# Schematic.net
KiCad netlist of a schematic drawn in Altium Designer
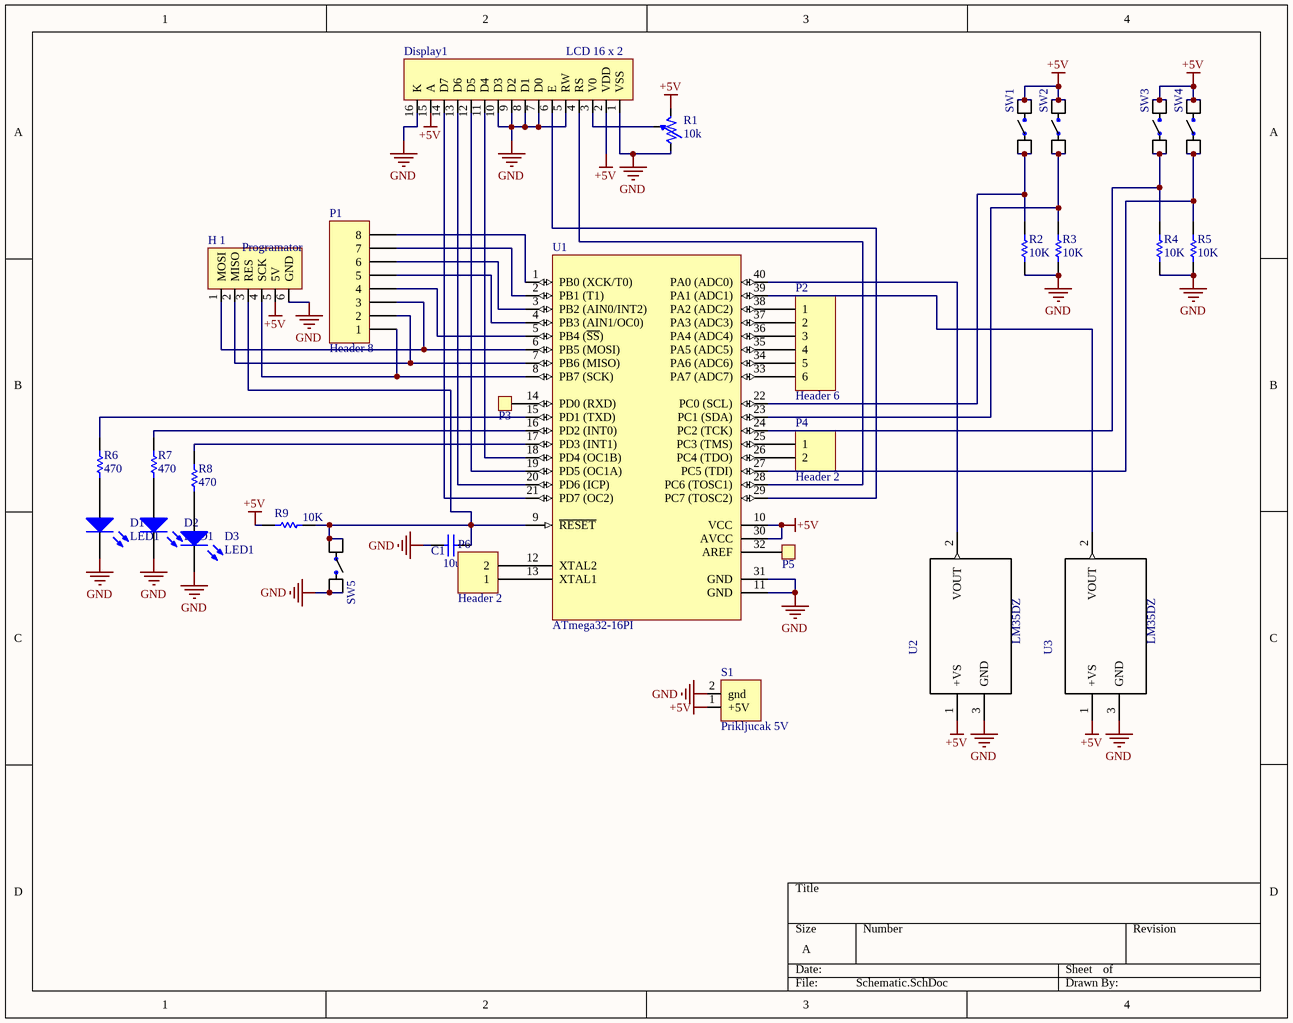
[diagram p0: Schematic.SchDoc]

(export (version "E")
  (design (tool "Eeschema 10.0.6"))
  (components
    (comp (ref "C1")
      (value "10uF")
      (footprint "RAD-0.3")
      (description "Capacitor")
      (fields (field (name "Comment") "Cap") (field (name "PUBLISHER") "Altium Limited"))
      (libsource (lib "Miscellaneous Devices") (part "Cap"))
    )
    (comp (ref "D1")
      (value "LED1")
      (footprint "LED-1")
      (description "Typical RED GaAs LED")
      (fields (field (name "PUBLISHER") "Altium Limited"))
      (libsource (lib "Miscellaneous Devices") (part "LED1"))
    )
    (comp (ref "D2")
      (value "LED1")
      (footprint "LED-1")
      (description "Typical RED GaAs LED")
      (fields (field (name "PUBLISHER") "Altium Limited"))
      (libsource (lib "Miscellaneous Devices") (part "LED1"))
    )
    (comp (ref "D3")
      (value "LED1")
      (footprint "LED-1")
      (description "Typical RED GaAs LED")
      (fields (field (name "PUBLISHER") "Altium Limited"))
      (libsource (lib "Miscellaneous Devices") (part "LED1"))
    )
    (comp (ref "Display1")
      (value "LCD 16 x 2")
      (footprint "LCD16x2")
      (libsource (lib "LIB-shematic") (part "LCD 16 X 2"))
    )
    (comp (ref "H 1")
      (value "Programator")
      (footprint "USBASP")
      (libsource (lib "LIB-shematic") (part "USBASP"))
    )
    (comp (ref "P1")
      (value "Header 8")
      (footprint "HDR1X8")
      (description "Header, 8-Pin")
      (fields (field (name "PUBLISHER") "Altium Limited"))
      (libsource (lib "Miscellaneous Connectors") (part "Header 8"))
    )
    (comp (ref "P2")
      (value "Header 6")
      (footprint "HDR1X6")
      (description "Header, 6-Pin")
      (fields (field (name "PUBLISHER") "Altium Limited"))
      (libsource (lib "Miscellaneous Connectors") (part "Header 6"))
    )
    (comp (ref "P3")
      (value "Header 1")
      (footprint "Header 1")
      (libsource (lib "LIB-schematic") (part "Header 1"))
    )
    (comp (ref "P4")
      (value "Header 2")
      (footprint "HDR1X2")
      (description "Header, 2-Pin")
      (fields (field (name "PUBLISHER") "Altium Limited"))
      (libsource (lib "") (part "Header 2_1"))
    )
    (comp (ref "P5")
      (value "Header 1")
      (footprint "Header 1")
      (libsource (lib "LIB-shematic") (part "Header 1"))
    )
    (comp (ref "P6")
      (value "Header 2")
      (footprint "HDR1X2")
      (description "Header, 2-Pin")
      (fields (field (name "PUBLISHER") "Altium Limited"))
      (libsource (lib "Miscellaneous Connectors") (part "Header 2"))
    )
    (comp (ref "R1") (value "10k") (footprint "ADJ_RES") (libsource (lib "LIB-shematic") (part "ADJ_RES")))
    (comp (ref "R2")
      (value "10K")
      (footprint "AXIAL-0.3")
      (description "Resistor")
      (fields (field (name "Comment") "Res1") (field (name "PUBLISHER") "Altium Limited"))
      (libsource (lib "Miscellaneous Devices") (part "Res1"))
    )
    (comp (ref "R3")
      (value "10K")
      (footprint "AXIAL-0.3")
      (description "Resistor")
      (fields (field (name "Comment") "Res1") (field (name "PUBLISHER") "Altium Limited"))
      (libsource (lib "Miscellaneous Devices") (part "Res1"))
    )
    (comp (ref "R4")
      (value "10K")
      (footprint "AXIAL-0.3")
      (description "Resistor")
      (fields (field (name "Comment") "Res1") (field (name "PUBLISHER") "Altium Limited"))
      (libsource (lib "Miscellaneous Devices") (part "Res1"))
    )
    (comp (ref "R5")
      (value "10K")
      (footprint "AXIAL-0.3")
      (description "Resistor")
      (fields (field (name "Comment") "Res1") (field (name "PUBLISHER") "Altium Limited"))
      (libsource (lib "Miscellaneous Devices") (part "Res1"))
    )
    (comp (ref "R6")
      (value "470")
      (footprint "AXIAL-0.3")
      (description "Resistor")
      (fields (field (name "Comment") "Res1") (field (name "PUBLISHER") "Altium Limited"))
      (libsource (lib "Miscellaneous Devices") (part "Res1"))
    )
    (comp (ref "R7")
      (value "470")
      (footprint "AXIAL-0.3")
      (description "Resistor")
      (fields (field (name "Comment") "Res1") (field (name "PUBLISHER") "Altium Limited"))
      (libsource (lib "Miscellaneous Devices") (part "Res1"))
    )
    (comp (ref "R8")
      (value "470")
      (footprint "AXIAL-0.3")
      (description "Resistor")
      (fields (field (name "Comment") "Res1") (field (name "PUBLISHER") "Altium Limited"))
      (libsource (lib "Miscellaneous Devices") (part "Res1"))
    )
    (comp (ref "R9")
      (value "10K")
      (footprint "AXIAL-0.3")
      (description "Resistor")
      (fields (field (name "Comment") "Res1") (field (name "PUBLISHER") "Altium Limited"))
      (libsource (lib "Miscellaneous Devices") (part "Res1"))
    )
    (comp (ref "S1")
      (value "Prikljucak 5V")
      (footprint "H 5V")
      (libsource (lib "LIB-schematic") (part "Header 5V"))
    )
    (comp (ref "SW1")
      (value "2-1437565-8")
      (footprint "*SW_SMD_2-1437565-8_4_4.50_6.00_6.00_5.00")
      (description "Tactile Switch SPST-NO Top Actuated Surface Mount")
      (fields (field (name "MF") "TE Connectivity"))
      (libsource (lib "LIB-shematic") (part "2-1437565-8"))
    )
    (comp (ref "SW2")
      (value "2-1437565-8")
      (footprint "*SW_SMD_2-1437565-8_4_4.50_6.00_6.00_5.00")
      (description "Tactile Switch SPST-NO Top Actuated Surface Mount")
      (fields (field (name "MF") "TE Connectivity"))
      (libsource (lib "LIB-shematic") (part "2-1437565-8"))
    )
    (comp (ref "SW3")
      (value "2-1437565-8")
      (footprint "*SW_SMD_2-1437565-8_4_4.50_6.00_6.00_5.00")
      (description "Tactile Switch SPST-NO Top Actuated Surface Mount")
      (fields (field (name "MF") "TE Connectivity"))
      (libsource (lib "LIB-shematic") (part "2-1437565-8"))
    )
    (comp (ref "SW4")
      (value "2-1437565-8")
      (footprint "*SW_SMD_2-1437565-8_4_4.50_6.00_6.00_5.00")
      (description "Tactile Switch SPST-NO Top Actuated Surface Mount")
      (fields (field (name "MF") "TE Connectivity"))
      (libsource (lib "LIB-shematic") (part "2-1437565-8"))
    )
    (comp (ref "SW5")
      (value "2-1437565-8")
      (footprint "*SW_SMD_2-1437565-8_4_4.50_6.00_6.00_5.00")
      (description "Tactile Switch SPST-NO Top Actuated Surface Mount")
      (fields (field (name "MF") "TE Connectivity"))
      (libsource (lib "LIB-shematic") (part "2-1437565-8"))
    )
    (comp (ref "U1")
      (value "ATmega32-16PI")
      (footprint "40P6")
      (description "8-Bit AVR Microcontroller with 32K Bytes of In-System Programmable Flash Memory")
      (fields (field (name "PUBLISHER") "Altium Limited"))
      (libsource (lib "Atmel Microcontroller 8-Bit AVR") (part "ATmega32-16PI"))
    )
    (comp (ref "U2")
      (value "LM35DZ")
      (footprint "*TO127P254X495-3P")
      (description "Temperature Sensor Analog, Local 0Â°C ~ 100Â°C 10mV/Â°C TO-92-3")
      (fields (field (name "MF") "Texas Instruments"))
      (libsource (lib "LIB-schematic") (part "LM35DZ"))
    )
    (comp (ref "U3")
      (value "LM35DZ")
      (footprint "*TO127P254X495-3P")
      (description "Temperature Sensor Analog, Local 0Â°C ~ 100Â°C 10mV/Â°C TO-92-3")
      (fields (field (name "MF") "Texas Instruments"))
      (libsource (lib "LIB-schematic") (part "LM35DZ"))
    )
  )
  (nets
    (net (code "1") (name "+5V") (class "Default")
      (node (ref "Display1") (pin "15") (pinfunction "A_15") (pintype "passive"))
      (node (ref "Display1") (pin "2") (pinfunction "VDD_2") (pintype "passive"))
      (node (ref "H 1") (pin "5") (pinfunction "5V_5") (pintype "passive"))
      (node (ref "R1") (pin "2") (pinfunction "2_2") (pintype "passive"))
      (node (ref "R9") (pin "1") (pinfunction "1_1") (pintype "passive"))
      (node (ref "S1") (pin "1") (pinfunction "+5V_1") (pintype "passive"))
      (node (ref "SW1") (pin "3") (pinfunction "3_3") (pintype "passive"))
      (node (ref "SW1") (pin "4") (pinfunction "4_4") (pintype "passive"))
      (node (ref "SW2") (pin "3") (pinfunction "3_3") (pintype "passive"))
      (node (ref "SW2") (pin "4") (pinfunction "4_4") (pintype "passive"))
      (node (ref "SW3") (pin "3") (pinfunction "3_3") (pintype "passive"))
      (node (ref "SW3") (pin "4") (pinfunction "4_4") (pintype "passive"))
      (node (ref "SW4") (pin "3") (pinfunction "3_3") (pintype "passive"))
      (node (ref "SW4") (pin "4") (pinfunction "4_4") (pintype "passive"))
      (node (ref "U1") (pin "10") (pinfunction "VCC_10") (pintype "power_in"))
      (node (ref "U1") (pin "30") (pinfunction "AVCC_30") (pintype "power_in"))
      (node (ref "U2") (pin "1") (pinfunction "+VS_1") (pintype "power_in"))
      (node (ref "U3") (pin "1") (pinfunction "+VS_1") (pintype "power_in"))
    )
    (net (code "2") (name "GND") (class "Default")
      (node (ref "C1") (pin "2") (pinfunction "2_2") (pintype "passive"))
      (node (ref "D1") (pin "2") (pinfunction "K_2") (pintype "passive"))
      (node (ref "D2") (pin "2") (pinfunction "K_2") (pintype "passive"))
      (node (ref "D3") (pin "2") (pinfunction "K_2") (pintype "passive"))
      (node (ref "Display1") (pin "1") (pinfunction "VSS_1") (pintype "passive"))
      (node (ref "Display1") (pin "10") (pinfunction "D3_10") (pintype "passive"))
      (node (ref "Display1") (pin "16") (pinfunction "K_16") (pintype "passive"))
      (node (ref "Display1") (pin "5") (pinfunction "RW_5") (pintype "passive"))
      (node (ref "Display1") (pin "7") (pinfunction "D0_7") (pintype "passive"))
      (node (ref "Display1") (pin "8") (pinfunction "D1_8") (pintype "passive"))
      (node (ref "Display1") (pin "9") (pinfunction "D2_9") (pintype "passive"))
      (node (ref "H 1") (pin "6") (pinfunction "GND_6") (pintype "passive"))
      (node (ref "R1") (pin "1") (pinfunction "1_1") (pintype "passive"))
      (node (ref "R2") (pin "1") (pinfunction "1_1") (pintype "passive"))
      (node (ref "R3") (pin "1") (pinfunction "1_1") (pintype "passive"))
      (node (ref "R4") (pin "1") (pinfunction "1_1") (pintype "passive"))
      (node (ref "R5") (pin "1") (pinfunction "1_1") (pintype "passive"))
      (node (ref "S1") (pin "2") (pinfunction "gnd_2") (pintype "passive"))
      (node (ref "SW5") (pin "3") (pinfunction "3_3") (pintype "passive"))
      (node (ref "SW5") (pin "4") (pinfunction "4_4") (pintype "passive"))
      (node (ref "U1") (pin "11") (pinfunction "GND_11") (pintype "power_in"))
      (node (ref "U1") (pin "31") (pinfunction "GND_31") (pintype "power_in"))
      (node (ref "U2") (pin "3") (pinfunction "GND_3") (pintype "passive"))
      (node (ref "U3") (pin "3") (pinfunction "GND_3") (pintype "passive"))
    )
    (net (code "3") (name "Net-(D1-A)") (class "Default")
      (node (ref "D1") (pin "1") (pinfunction "A_1") (pintype "passive"))
      (node (ref "R6") (pin "1") (pinfunction "1_1") (pintype "passive"))
    )
    (net (code "4") (name "Net-(D2-A)") (class "Default")
      (node (ref "D2") (pin "1") (pinfunction "A_1") (pintype "passive"))
      (node (ref "R7") (pin "1") (pinfunction "1_1") (pintype "passive"))
    )
    (net (code "5") (name "Net-(D3-A)") (class "Default")
      (node (ref "D3") (pin "1") (pinfunction "A_1") (pintype "passive"))
      (node (ref "R8") (pin "1") (pinfunction "1_1") (pintype "passive"))
    )
    (net (code "6") (name "Net-(Display1-D4)") (class "Default")
      (node (ref "Display1") (pin "11") (pinfunction "D4_11") (pintype "passive"))
      (node (ref "U1") (pin "18") (pinfunction "PD4_(OC1B)_18") (pintype "bidirectional"))
    )
    (net (code "7") (name "Net-(Display1-D5)") (class "Default")
      (node (ref "Display1") (pin "12") (pinfunction "D5_12") (pintype "passive"))
      (node (ref "U1") (pin "19") (pinfunction "PD5_(OC1A)_19") (pintype "bidirectional"))
    )
    (net (code "8") (name "Net-(Display1-D6)") (class "Default")
      (node (ref "Display1") (pin "13") (pinfunction "D6_13") (pintype "passive"))
      (node (ref "U1") (pin "20") (pinfunction "PD6_(ICP)_20") (pintype "bidirectional"))
    )
    (net (code "9") (name "Net-(Display1-D7)") (class "Default")
      (node (ref "Display1") (pin "14") (pinfunction "D7_14") (pintype "passive"))
      (node (ref "U1") (pin "21") (pinfunction "PD7_(OC2)_21") (pintype "bidirectional"))
    )
    (net (code "10") (name "Net-(Display1-E)") (class "Default")
      (node (ref "Display1") (pin "6") (pinfunction "E_6") (pintype "passive"))
      (node (ref "U1") (pin "29") (pinfunction "PC7_(TOSC2)_29") (pintype "bidirectional"))
    )
    (net (code "11") (name "Net-(Display1-RS)") (class "Default")
      (node (ref "Display1") (pin "4") (pinfunction "RS_4") (pintype "passive"))
      (node (ref "U1") (pin "28") (pinfunction "PC6_(TOSC1)_28") (pintype "bidirectional"))
    )
    (net (code "12") (name "Net-(Display1-V0)") (class "Default")
      (node (ref "Display1") (pin "3") (pinfunction "V0_3") (pintype "passive"))
      (node (ref "R1") (pin "3") (pinfunction "3_3") (pintype "passive"))
    )
    (net (code "13") (name "Net-(H 1-MISO)") (class "Default")
      (node (ref "H 1") (pin "2") (pinfunction "MISO_2") (pintype "passive"))
      (node (ref "P1") (pin "2") (pinfunction "2_2") (pintype "passive"))
      (node (ref "U1") (pin "7") (pinfunction "PB6_(MISO)_7") (pintype "bidirectional"))
    )
    (net (code "14") (name "Net-(H 1-MOSI)") (class "Default")
      (node (ref "H 1") (pin "1") (pinfunction "MOSI_1") (pintype "passive"))
      (node (ref "P1") (pin "3") (pinfunction "3_3") (pintype "passive"))
      (node (ref "U1") (pin "6") (pinfunction "PB5_(MOSI)_6") (pintype "bidirectional"))
    )
    (net (code "15") (name "Net-(H 1-RES)") (class "Default")
      (node (ref "C1") (pin "1") (pinfunction "1_1") (pintype "passive"))
      (node (ref "H 1") (pin "3") (pinfunction "RES_3") (pintype "passive"))
      (node (ref "R9") (pin "2") (pinfunction "2_2") (pintype "passive"))
      (node (ref "SW5") (pin "1") (pinfunction "1_1") (pintype "passive"))
      (node (ref "SW5") (pin "2") (pinfunction "2_2") (pintype "passive"))
      (node (ref "U1") (pin "9") (pinfunction "~{RESET}_9") (pintype "input"))
    )
    (net (code "16") (name "Net-(H 1-SCK)") (class "Default")
      (node (ref "H 1") (pin "4") (pinfunction "SCK_4") (pintype "passive"))
      (node (ref "P1") (pin "1") (pinfunction "1_1") (pintype "passive"))
      (node (ref "U1") (pin "8") (pinfunction "PB7_(SCK)_8") (pintype "bidirectional"))
    )
    (net (code "17") (name "Net-(U1-AREF)") (class "Default")
      (node (ref "P5") (pin "1") (pinfunction "1_1") (pintype "passive"))
      (node (ref "U1") (pin "32") (pinfunction "AREF_32") (pintype "passive"))
    )
    (net (code "18") (name "Net-(U1-PA0_(ADC0))") (class "Default")
      (node (ref "U1") (pin "40") (pinfunction "PA0_(ADC0)_40") (pintype "bidirectional"))
      (node (ref "U2") (pin "2") (pinfunction "VOUT_2") (pintype "output"))
    )
    (net (code "19") (name "Net-(U1-PA1_(ADC1))") (class "Default")
      (node (ref "U1") (pin "39") (pinfunction "PA1_(ADC1)_39") (pintype "bidirectional"))
      (node (ref "U3") (pin "2") (pinfunction "VOUT_2") (pintype "output"))
    )
    (net (code "20") (name "Net-(U1-PA2_(ADC2))") (class "Default")
      (node (ref "P2") (pin "1") (pinfunction "1_1") (pintype "passive"))
      (node (ref "U1") (pin "38") (pinfunction "PA2_(ADC2)_38") (pintype "bidirectional"))
    )
    (net (code "21") (name "Net-(U1-PA3_(ADC3))") (class "Default")
      (node (ref "P2") (pin "2") (pinfunction "2_2") (pintype "passive"))
      (node (ref "U1") (pin "37") (pinfunction "PA3_(ADC3)_37") (pintype "bidirectional"))
    )
    (net (code "22") (name "Net-(U1-PA4_(ADC4))") (class "Default")
      (node (ref "P2") (pin "3") (pinfunction "3_3") (pintype "passive"))
      (node (ref "U1") (pin "36") (pinfunction "PA4_(ADC4)_36") (pintype "bidirectional"))
    )
    (net (code "23") (name "Net-(U1-PA5_(ADC5))") (class "Default")
      (node (ref "P2") (pin "4") (pinfunction "4_4") (pintype "passive"))
      (node (ref "U1") (pin "35") (pinfunction "PA5_(ADC5)_35") (pintype "bidirectional"))
    )
    (net (code "24") (name "Net-(U1-PA6_(ADC6))") (class "Default")
      (node (ref "P2") (pin "5") (pinfunction "5_5") (pintype "passive"))
      (node (ref "U1") (pin "34") (pinfunction "PA6_(ADC6)_34") (pintype "bidirectional"))
    )
    (net (code "25") (name "Net-(U1-PA7_(ADC7))") (class "Default")
      (node (ref "P2") (pin "6") (pinfunction "6_6") (pintype "passive"))
      (node (ref "U1") (pin "33") (pinfunction "PA7_(ADC7)_33") (pintype "bidirectional"))
    )
    (net (code "26") (name "Net-(U1-PB0_(XCK{slash}T0))") (class "Default")
      (node (ref "P1") (pin "8") (pinfunction "8_8") (pintype "passive"))
      (node (ref "U1") (pin "1") (pinfunction "PB0_(XCK/T0)_1") (pintype "bidirectional"))
    )
    (net (code "27") (name "Net-(U1-PB1_(T1))") (class "Default")
      (node (ref "P1") (pin "7") (pinfunction "7_7") (pintype "passive"))
      (node (ref "U1") (pin "2") (pinfunction "PB1_(T1)_2") (pintype "bidirectional"))
    )
    (net (code "28") (name "Net-(U1-PB2_(AIN0{slash}INT2))") (class "Default")
      (node (ref "P1") (pin "6") (pinfunction "6_6") (pintype "passive"))
      (node (ref "U1") (pin "3") (pinfunction "PB2_(AIN0/INT2)_3") (pintype "bidirectional"))
    )
    (net (code "29") (name "Net-(U1-PB3_(AIN1{slash}OC0))") (class "Default")
      (node (ref "P1") (pin "5") (pinfunction "5_5") (pintype "passive"))
      (node (ref "U1") (pin "4") (pinfunction "PB3_(AIN1/OC0)_4") (pintype "bidirectional"))
    )
    (net (code "30") (name "Net-(U1-PB4_(~{SS}))") (class "Default")
      (node (ref "P1") (pin "4") (pinfunction "4_4") (pintype "passive"))
      (node (ref "U1") (pin "5") (pinfunction "PB4_(~{SS})_5") (pintype "bidirectional"))
    )
    (net (code "31") (name "Net-(U1-PC0_(SCL))") (class "Default")
      (node (ref "R2") (pin "2") (pinfunction "2_2") (pintype "passive"))
      (node (ref "SW1") (pin "1") (pinfunction "1_1") (pintype "passive"))
      (node (ref "SW1") (pin "2") (pinfunction "2_2") (pintype "passive"))
      (node (ref "U1") (pin "22") (pinfunction "PC0_(SCL)_22") (pintype "bidirectional"))
    )
    (net (code "32") (name "Net-(U1-PC1_(SDA))") (class "Default")
      (node (ref "R3") (pin "2") (pinfunction "2_2") (pintype "passive"))
      (node (ref "SW2") (pin "1") (pinfunction "1_1") (pintype "passive"))
      (node (ref "SW2") (pin "2") (pinfunction "2_2") (pintype "passive"))
      (node (ref "U1") (pin "23") (pinfunction "PC1_(SDA)_23") (pintype "bidirectional"))
    )
    (net (code "33") (name "Net-(U1-PC2_(TCK))") (class "Default")
      (node (ref "R4") (pin "2") (pinfunction "2_2") (pintype "passive"))
      (node (ref "SW3") (pin "1") (pinfunction "1_1") (pintype "passive"))
      (node (ref "SW3") (pin "2") (pinfunction "2_2") (pintype "passive"))
      (node (ref "U1") (pin "24") (pinfunction "PC2_(TCK)_24") (pintype "bidirectional"))
    )
    (net (code "34") (name "Net-(U1-PC3_(TMS))") (class "Default")
      (node (ref "P4") (pin "1") (pinfunction "1_1") (pintype "passive"))
      (node (ref "U1") (pin "25") (pinfunction "PC3_(TMS)_25") (pintype "bidirectional"))
    )
    (net (code "35") (name "Net-(U1-PC4_(TDO))") (class "Default")
      (node (ref "P4") (pin "2") (pinfunction "2_2") (pintype "passive"))
      (node (ref "U1") (pin "26") (pinfunction "PC4_(TDO)_26") (pintype "bidirectional"))
    )
    (net (code "36") (name "Net-(U1-PC5_(TDI))") (class "Default")
      (node (ref "R5") (pin "2") (pinfunction "2_2") (pintype "passive"))
      (node (ref "SW4") (pin "1") (pinfunction "1_1") (pintype "passive"))
      (node (ref "SW4") (pin "2") (pinfunction "2_2") (pintype "passive"))
      (node (ref "U1") (pin "27") (pinfunction "PC5_(TDI)_27") (pintype "bidirectional"))
    )
    (net (code "37") (name "Net-(U1-PD0_(RXD))") (class "Default")
      (node (ref "P3") (pin "1") (pinfunction "1_1") (pintype "passive"))
      (node (ref "U1") (pin "14") (pinfunction "PD0_(RXD)_14") (pintype "bidirectional"))
    )
    (net (code "38") (name "Net-(U1-PD1_(TXD))") (class "Default")
      (node (ref "R6") (pin "2") (pinfunction "2_2") (pintype "passive"))
      (node (ref "U1") (pin "15") (pinfunction "PD1_(TXD)_15") (pintype "bidirectional"))
    )
    (net (code "39") (name "Net-(U1-PD2_(INT0))") (class "Default")
      (node (ref "R7") (pin "2") (pinfunction "2_2") (pintype "passive"))
      (node (ref "U1") (pin "16") (pinfunction "PD2_(INT0)_16") (pintype "bidirectional"))
    )
    (net (code "40") (name "Net-(U1-PD3_(INT1))") (class "Default")
      (node (ref "R8") (pin "2") (pinfunction "2_2") (pintype "passive"))
      (node (ref "U1") (pin "17") (pinfunction "PD3_(INT1)_17") (pintype "bidirectional"))
    )
    (net (code "41") (name "Net-(U1-XTAL1)") (class "Default")
      (node (ref "P6") (pin "1") (pinfunction "1_1") (pintype "passive"))
      (node (ref "U1") (pin "13") (pinfunction "XTAL1_13") (pintype "passive"))
    )
    (net (code "42") (name "Net-(U1-XTAL2)") (class "Default")
      (node (ref "P6") (pin "2") (pinfunction "2_2") (pintype "passive"))
      (node (ref "U1") (pin "12") (pinfunction "XTAL2_12") (pintype "passive"))
    )
  )
)
